# light-sink.net
KiCad netlist of a schematic drawn in EAGLE
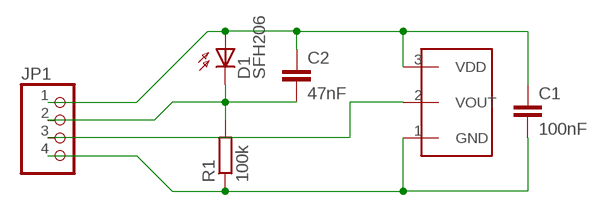
[diagram p0: schematic, sheet 1]

(export (version "E")
  (design (tool "Eeschema 10.0.6"))
  (components
    (comp (ref "C1")
      (value "100nF")
      (footprint "eagle-import:C050-035X075")
      (libsource (lib "eagle-import") (part "C-EU050-035X075"))
    )
    (comp (ref "C2")
      (value "47nF")
      (footprint "eagle-import:C050-035X075")
      (libsource (lib "eagle-import") (part "C-EU050-035X075"))
    )
    (comp (ref "D1")
      (value "SFH206")
      (footprint "eagle-import:SFH206")
      (fields (field (name "MPN") "SFH206K"))
      (libsource (lib "eagle-import") (part "SFH206"))
    )
    (comp (ref "JP1")
      (value "PINHD-1X4")
      (footprint "eagle-import:1X04")
      (libsource (lib "eagle-import") (part "PINHD-1X4"))
    )
    (comp (ref "R1")
      (value "100k")
      (footprint "eagle-import:0207_10")
      (libsource (lib "eagle-import") (part "R-EU_0207/10"))
    )
    (comp (ref "TSINK")
      (value "MCP9701-TO92")
      (footprint "eagle-import:TO92")
      (libsource (lib "eagle-import") (part "MCP9701-TO92"))
    )
  )
  (nets
    (net (code "1") (name "Net-(D1-C)") (class "Default")
      (node (ref "C2") (pin "2") (pinfunction "2_2") (pintype "passive"))
      (node (ref "D1") (pin "K") (pinfunction "C_K") (pintype "passive"))
      (node (ref "JP1") (pin "2") (pinfunction "2_2") (pintype "passive"))
      (node (ref "R1") (pin "2") (pinfunction "2_2") (pintype "passive"))
    )
    (net (code "2") (name "Net-(TSINK-GND)") (class "Default")
      (node (ref "C1") (pin "2") (pinfunction "2_2") (pintype "passive"))
      (node (ref "JP1") (pin "4") (pinfunction "4_4") (pintype "passive"))
      (node (ref "R1") (pin "1") (pinfunction "1_1") (pintype "passive"))
      (node (ref "TSINK") (pin "1") (pinfunction "GND_1") (pintype "bidirectional"))
    )
    (net (code "3") (name "Net-(TSINK-VDD)") (class "Default")
      (node (ref "C1") (pin "1") (pinfunction "1_1") (pintype "passive"))
      (node (ref "C2") (pin "1") (pinfunction "1_1") (pintype "passive"))
      (node (ref "D1") (pin "A") (pinfunction "A_A") (pintype "passive"))
      (node (ref "JP1") (pin "1") (pinfunction "1_1") (pintype "passive"))
      (node (ref "TSINK") (pin "3") (pinfunction "VDD_3") (pintype "bidirectional"))
    )
    (net (code "4") (name "Net-(TSINK-VOUT)") (class "Default")
      (node (ref "JP1") (pin "3") (pinfunction "3_3") (pintype "passive"))
      (node (ref "TSINK") (pin "2") (pinfunction "VOUT_2") (pintype "bidirectional"))
    )
  )
)
